# PowerBoard.net
KiCad netlist of a schematic drawn in Altium Designer
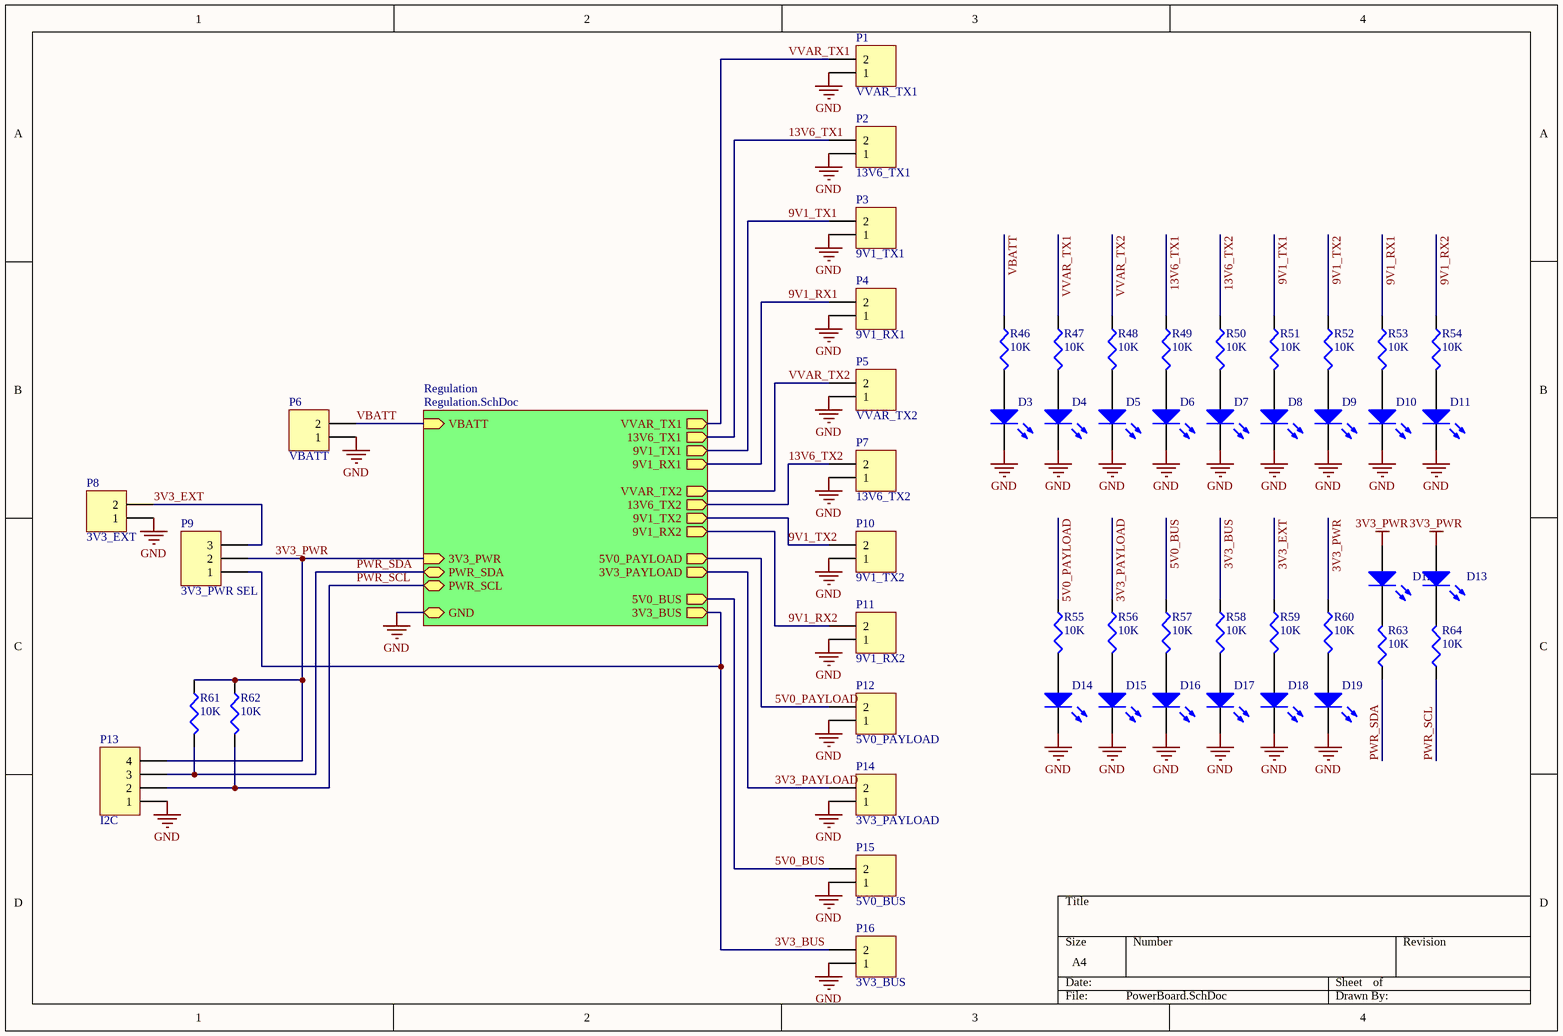
[diagram p0: PowerBoard.SchDoc]

(export (version "E")
  (design (tool "Eeschema 10.0.6"))
  (components
    (comp (ref "D3")
      (value "LED0")
      (footprint "R0805M")
      (description "Typical INFRARED GaAs LED")
      (fields (field (name "PUBLISHER") "Altium Limited"))
      (libsource (lib "Miscellaneous Devices") (part "LED0"))
    )
    (comp (ref "D4")
      (value "LED0")
      (footprint "R0805M")
      (description "Typical INFRARED GaAs LED")
      (fields (field (name "PUBLISHER") "Altium Limited"))
      (libsource (lib "Miscellaneous Devices") (part "LED0"))
    )
    (comp (ref "D5")
      (value "LED0")
      (footprint "R0805M")
      (description "Typical INFRARED GaAs LED")
      (fields (field (name "PUBLISHER") "Altium Limited"))
      (libsource (lib "Miscellaneous Devices") (part "LED0"))
    )
    (comp (ref "D6")
      (value "LED0")
      (footprint "R0805M")
      (description "Typical INFRARED GaAs LED")
      (fields (field (name "PUBLISHER") "Altium Limited"))
      (libsource (lib "Miscellaneous Devices") (part "LED0"))
    )
    (comp (ref "D7")
      (value "LED0")
      (footprint "R0805M")
      (description "Typical INFRARED GaAs LED")
      (fields (field (name "PUBLISHER") "Altium Limited"))
      (libsource (lib "Miscellaneous Devices") (part "LED0"))
    )
    (comp (ref "D8")
      (value "LED0")
      (footprint "R0805M")
      (description "Typical INFRARED GaAs LED")
      (fields (field (name "PUBLISHER") "Altium Limited"))
      (libsource (lib "Miscellaneous Devices") (part "LED0"))
    )
    (comp (ref "D9")
      (value "LED0")
      (footprint "R0805M")
      (description "Typical INFRARED GaAs LED")
      (fields (field (name "PUBLISHER") "Altium Limited"))
      (libsource (lib "Miscellaneous Devices") (part "LED0"))
    )
    (comp (ref "D10")
      (value "LED0")
      (footprint "R0805M")
      (description "Typical INFRARED GaAs LED")
      (fields (field (name "PUBLISHER") "Altium Limited"))
      (libsource (lib "Miscellaneous Devices") (part "LED0"))
    )
    (comp (ref "D11")
      (value "LED0")
      (footprint "R0805M")
      (description "Typical INFRARED GaAs LED")
      (fields (field (name "PUBLISHER") "Altium Limited"))
      (libsource (lib "Miscellaneous Devices") (part "LED0"))
    )
    (comp (ref "D12")
      (value "LED0")
      (footprint "R0805M")
      (description "Typical INFRARED GaAs LED")
      (fields (field (name "PUBLISHER") "Altium Limited"))
      (libsource (lib "Miscellaneous Devices") (part "LED0"))
    )
    (comp (ref "D13")
      (value "LED0")
      (footprint "R0805M")
      (description "Typical INFRARED GaAs LED")
      (fields (field (name "PUBLISHER") "Altium Limited"))
      (libsource (lib "Miscellaneous Devices") (part "LED0"))
    )
    (comp (ref "D14")
      (value "LED0")
      (footprint "R0805M")
      (description "Typical INFRARED GaAs LED")
      (fields (field (name "PUBLISHER") "Altium Limited"))
      (libsource (lib "Miscellaneous Devices") (part "LED0"))
    )
    (comp (ref "D15")
      (value "LED0")
      (footprint "R0805M")
      (description "Typical INFRARED GaAs LED")
      (fields (field (name "PUBLISHER") "Altium Limited"))
      (libsource (lib "Miscellaneous Devices") (part "LED0"))
    )
    (comp (ref "D16")
      (value "LED0")
      (footprint "R0805M")
      (description "Typical INFRARED GaAs LED")
      (fields (field (name "PUBLISHER") "Altium Limited"))
      (libsource (lib "Miscellaneous Devices") (part "LED0"))
    )
    (comp (ref "D17")
      (value "LED0")
      (footprint "R0805M")
      (description "Typical INFRARED GaAs LED")
      (fields (field (name "PUBLISHER") "Altium Limited"))
      (libsource (lib "Miscellaneous Devices") (part "LED0"))
    )
    (comp (ref "D18")
      (value "LED0")
      (footprint "R0805M")
      (description "Typical INFRARED GaAs LED")
      (fields (field (name "PUBLISHER") "Altium Limited"))
      (libsource (lib "Miscellaneous Devices") (part "LED0"))
    )
    (comp (ref "D19")
      (value "LED0")
      (footprint "R0805M")
      (description "Typical INFRARED GaAs LED")
      (fields (field (name "PUBLISHER") "Altium Limited"))
      (libsource (lib "Miscellaneous Devices") (part "LED0"))
    )
    (comp (ref "P1")
      (value "VVAR_TX1")
      (footprint "200MIL TERMINAL")
      (description "Header, 2-Pin")
      (fields (field (name "PUBLISHER") "Altium Limited"))
      (libsource (lib "Miscellaneous Connectors") (part "Header 2"))
    )
    (comp (ref "P2")
      (value "13V6_TX1")
      (footprint "200MIL TERMINAL")
      (description "Header, 2-Pin")
      (fields (field (name "PUBLISHER") "Altium Limited"))
      (libsource (lib "Miscellaneous Connectors") (part "Header 2"))
    )
    (comp (ref "P3")
      (value "9V1_TX1")
      (footprint "200MIL TERMINAL")
      (description "Header, 2-Pin")
      (fields (field (name "PUBLISHER") "Altium Limited"))
      (libsource (lib "Miscellaneous Connectors") (part "Header 2"))
    )
    (comp (ref "P4")
      (value "9V1_RX1")
      (footprint "200MIL TERMINAL")
      (description "Header, 2-Pin")
      (fields (field (name "PUBLISHER") "Altium Limited"))
      (libsource (lib "Miscellaneous Connectors") (part "Header 2"))
    )
    (comp (ref "P5")
      (value "VVAR_TX2")
      (footprint "200MIL TERMINAL")
      (description "Header, 2-Pin")
      (fields (field (name "PUBLISHER") "Altium Limited"))
      (libsource (lib "Miscellaneous Connectors") (part "Header 2"))
    )
    (comp (ref "P6")
      (value "VBATT")
      (footprint "200MIL TERMINAL")
      (description "Header, 2-Pin")
      (fields (field (name "PUBLISHER") "Altium Limited"))
      (libsource (lib "") (part "Header 2_1"))
    )
    (comp (ref "P7")
      (value "13V6_TX2")
      (footprint "200MIL TERMINAL")
      (description "Header, 2-Pin")
      (fields (field (name "PUBLISHER") "Altium Limited"))
      (libsource (lib "Miscellaneous Connectors") (part "Header 2"))
    )
    (comp (ref "P8")
      (value "3V3_EXT")
      (footprint "200MIL TERMINAL")
      (description "Header, 2-Pin")
      (fields (field (name "PUBLISHER") "Altium Limited"))
      (libsource (lib "") (part "Header 2_1"))
    )
    (comp (ref "P9")
      (value "3V3_PWR SEL")
      (footprint "HDR1X3")
      (description "Header, 3-Pin")
      (fields (field (name "PUBLISHER") "Altium Limited"))
      (libsource (lib "Miscellaneous Connectors") (part "Header 3"))
    )
    (comp (ref "P10")
      (value "9V1_TX2")
      (footprint "200MIL TERMINAL")
      (description "Header, 2-Pin")
      (fields (field (name "PUBLISHER") "Altium Limited"))
      (libsource (lib "Miscellaneous Connectors") (part "Header 2"))
    )
    (comp (ref "P11")
      (value "9V1_RX2")
      (footprint "200MIL TERMINAL")
      (description "Header, 2-Pin")
      (fields (field (name "PUBLISHER") "Altium Limited"))
      (libsource (lib "Miscellaneous Connectors") (part "Header 2"))
    )
    (comp (ref "P12")
      (value "5V0_PAYLOAD")
      (footprint "200MIL TERMINAL")
      (description "Header, 2-Pin")
      (fields (field (name "PUBLISHER") "Altium Limited"))
      (libsource (lib "Miscellaneous Connectors") (part "Header 2"))
    )
    (comp (ref "P13")
      (value "I2C")
      (footprint "HDR1X4")
      (description "Header, 4-Pin")
      (fields (field (name "PUBLISHER") "Altium Limited"))
      (libsource (lib "Miscellaneous Connectors") (part "Header 4"))
    )
    (comp (ref "P14")
      (value "3V3_PAYLOAD")
      (footprint "200MIL TERMINAL")
      (description "Header, 2-Pin")
      (fields (field (name "PUBLISHER") "Altium Limited"))
      (libsource (lib "Miscellaneous Connectors") (part "Header 2"))
    )
    (comp (ref "P15")
      (value "5V0_BUS")
      (footprint "200MIL TERMINAL")
      (description "Header, 2-Pin")
      (fields (field (name "PUBLISHER") "Altium Limited"))
      (libsource (lib "Miscellaneous Connectors") (part "Header 2"))
    )
    (comp (ref "P16")
      (value "3V3_BUS")
      (footprint "200MIL TERMINAL")
      (description "Header, 2-Pin")
      (fields (field (name "PUBLISHER") "Altium Limited"))
      (libsource (lib "Miscellaneous Connectors") (part "Header 2"))
    )
    (comp (ref "R46")
      (value "10K")
      (footprint "R0402M")
      (description "Resistor")
      (fields (field (name "PUBLISHER") "Altium Limited"))
      (libsource (lib "Miscellaneous Devices") (part "Res3"))
    )
    (comp (ref "R47")
      (value "10K")
      (footprint "R0402M")
      (description "Resistor")
      (fields (field (name "PUBLISHER") "Altium Limited"))
      (libsource (lib "Miscellaneous Devices") (part "Res3"))
    )
    (comp (ref "R48")
      (value "10K")
      (footprint "R0402M")
      (description "Resistor")
      (fields (field (name "PUBLISHER") "Altium Limited"))
      (libsource (lib "Miscellaneous Devices") (part "Res3"))
    )
    (comp (ref "R49")
      (value "10K")
      (footprint "R0402M")
      (description "Resistor")
      (fields (field (name "PUBLISHER") "Altium Limited"))
      (libsource (lib "Miscellaneous Devices") (part "Res3"))
    )
    (comp (ref "R50")
      (value "10K")
      (footprint "R0402M")
      (description "Resistor")
      (fields (field (name "PUBLISHER") "Altium Limited"))
      (libsource (lib "Miscellaneous Devices") (part "Res3"))
    )
    (comp (ref "R51")
      (value "10K")
      (footprint "R0402M")
      (description "Resistor")
      (fields (field (name "PUBLISHER") "Altium Limited"))
      (libsource (lib "Miscellaneous Devices") (part "Res3"))
    )
    (comp (ref "R52")
      (value "10K")
      (footprint "R0402M")
      (description "Resistor")
      (fields (field (name "PUBLISHER") "Altium Limited"))
      (libsource (lib "Miscellaneous Devices") (part "Res3"))
    )
    (comp (ref "R53")
      (value "10K")
      (footprint "R0402M")
      (description "Resistor")
      (fields (field (name "PUBLISHER") "Altium Limited"))
      (libsource (lib "Miscellaneous Devices") (part "Res3"))
    )
    (comp (ref "R54")
      (value "10K")
      (footprint "R0402M")
      (description "Resistor")
      (fields (field (name "PUBLISHER") "Altium Limited"))
      (libsource (lib "Miscellaneous Devices") (part "Res3"))
    )
    (comp (ref "R55")
      (value "10K")
      (footprint "R0402M")
      (description "Resistor")
      (fields (field (name "PUBLISHER") "Altium Limited"))
      (libsource (lib "Miscellaneous Devices") (part "Res3"))
    )
    (comp (ref "R56")
      (value "10K")
      (footprint "R0402M")
      (description "Resistor")
      (fields (field (name "PUBLISHER") "Altium Limited"))
      (libsource (lib "Miscellaneous Devices") (part "Res3"))
    )
    (comp (ref "R57")
      (value "10K")
      (footprint "R0402M")
      (description "Resistor")
      (fields (field (name "PUBLISHER") "Altium Limited"))
      (libsource (lib "Miscellaneous Devices") (part "Res3"))
    )
    (comp (ref "R58")
      (value "10K")
      (footprint "R0402M")
      (description "Resistor")
      (fields (field (name "PUBLISHER") "Altium Limited"))
      (libsource (lib "Miscellaneous Devices") (part "Res3"))
    )
    (comp (ref "R59")
      (value "10K")
      (footprint "R0402M")
      (description "Resistor")
      (fields (field (name "PUBLISHER") "Altium Limited"))
      (libsource (lib "Miscellaneous Devices") (part "Res3"))
    )
    (comp (ref "R60")
      (value "10K")
      (footprint "R0402M")
      (description "Resistor")
      (fields (field (name "PUBLISHER") "Altium Limited"))
      (libsource (lib "Miscellaneous Devices") (part "Res3"))
    )
    (comp (ref "R61")
      (value "10K")
      (footprint "R0402M")
      (description "Resistor")
      (fields (field (name "PUBLISHER") "Altium Limited"))
      (libsource (lib "Miscellaneous Devices") (part "Res3"))
    )
    (comp (ref "R62")
      (value "10K")
      (footprint "R0402M")
      (description "Resistor")
      (fields (field (name "PUBLISHER") "Altium Limited"))
      (libsource (lib "Miscellaneous Devices") (part "Res3"))
    )
    (comp (ref "R63")
      (value "10K")
      (footprint "R0402M")
      (description "Resistor")
      (fields (field (name "PUBLISHER") "Altium Limited"))
      (libsource (lib "Miscellaneous Devices") (part "Res3"))
    )
    (comp (ref "R64")
      (value "10K")
      (footprint "R0402M")
      (description "Resistor")
      (fields (field (name "PUBLISHER") "Altium Limited"))
      (libsource (lib "Miscellaneous Devices") (part "Res3"))
    )
  )
  (nets
    (net (code "1") (name "/3V3_BUS") (class "Default")
      (node (ref "P16") (pin "2") (pinfunction "2_2") (pintype "passive"))
      (node (ref "P9") (pin "1") (pinfunction "1_1") (pintype "passive"))
      (node (ref "R58") (pin "1") (pinfunction "1_1") (pintype "passive"))
    )
    (net (code "2") (name "/3V3_EXT") (class "Default")
      (node (ref "P8") (pin "2") (pinfunction "2_2") (pintype "passive"))
      (node (ref "P9") (pin "3") (pinfunction "3_3") (pintype "passive"))
      (node (ref "R59") (pin "1") (pinfunction "1_1") (pintype "passive"))
    )
    (net (code "3") (name "/3V3_PAYLOAD") (class "Default")
      (node (ref "P14") (pin "2") (pinfunction "2_2") (pintype "passive"))
      (node (ref "R56") (pin "1") (pinfunction "1_1") (pintype "passive"))
    )
    (net (code "4") (name "/5V0_BUS") (class "Default")
      (node (ref "P15") (pin "2") (pinfunction "2_2") (pintype "passive"))
      (node (ref "R57") (pin "1") (pinfunction "1_1") (pintype "passive"))
    )
    (net (code "5") (name "/5V0_PAYLOAD") (class "Default")
      (node (ref "P12") (pin "2") (pinfunction "2_2") (pintype "passive"))
      (node (ref "R55") (pin "1") (pinfunction "1_1") (pintype "passive"))
    )
    (net (code "6") (name "/9V1_RX1") (class "Default")
      (node (ref "P4") (pin "2") (pinfunction "2_2") (pintype "passive"))
      (node (ref "R53") (pin "1") (pinfunction "1_1") (pintype "passive"))
    )
    (net (code "7") (name "/9V1_RX2") (class "Default")
      (node (ref "P11") (pin "2") (pinfunction "2_2") (pintype "passive"))
      (node (ref "R54") (pin "1") (pinfunction "1_1") (pintype "passive"))
    )
    (net (code "8") (name "/9V1_TX1") (class "Default")
      (node (ref "P3") (pin "2") (pinfunction "2_2") (pintype "passive"))
      (node (ref "R51") (pin "1") (pinfunction "1_1") (pintype "passive"))
    )
    (net (code "9") (name "/9V1_TX2") (class "Default")
      (node (ref "P10") (pin "2") (pinfunction "2_2") (pintype "passive"))
      (node (ref "R52") (pin "1") (pinfunction "1_1") (pintype "passive"))
    )
    (net (code "10") (name "/13V6_TX1") (class "Default")
      (node (ref "P2") (pin "2") (pinfunction "2_2") (pintype "passive"))
      (node (ref "R49") (pin "1") (pinfunction "1_1") (pintype "passive"))
    )
    (net (code "11") (name "/13V6_TX2") (class "Default")
      (node (ref "P7") (pin "2") (pinfunction "2_2") (pintype "passive"))
      (node (ref "R50") (pin "1") (pinfunction "1_1") (pintype "passive"))
    )
    (net (code "12") (name "/PWR_SCL") (class "Default")
      (node (ref "P13") (pin "2") (pinfunction "2_2") (pintype "passive"))
      (node (ref "R62") (pin "2") (pinfunction "2_2") (pintype "passive"))
      (node (ref "R64") (pin "1") (pinfunction "1_1") (pintype "passive"))
    )
    (net (code "13") (name "/PWR_SDA") (class "Default")
      (node (ref "P13") (pin "3") (pinfunction "3_3") (pintype "passive"))
      (node (ref "R61") (pin "2") (pinfunction "2_2") (pintype "passive"))
      (node (ref "R63") (pin "1") (pinfunction "1_1") (pintype "passive"))
    )
    (net (code "14") (name "/VBATT") (class "Default")
      (node (ref "P6") (pin "2") (pinfunction "2_2") (pintype "passive"))
      (node (ref "R46") (pin "1") (pinfunction "1_1") (pintype "passive"))
    )
    (net (code "15") (name "/VVAR_TX1") (class "Default")
      (node (ref "P1") (pin "2") (pinfunction "2_2") (pintype "passive"))
      (node (ref "R47") (pin "1") (pinfunction "1_1") (pintype "passive"))
    )
    (net (code "16") (name "/VVAR_TX2") (class "Default")
      (node (ref "P5") (pin "2") (pinfunction "2_2") (pintype "passive"))
      (node (ref "R48") (pin "1") (pinfunction "1_1") (pintype "passive"))
    )
    (net (code "17") (name "3V3_PWR") (class "Default")
      (node (ref "D12") (pin "1") (pinfunction "A_1") (pintype "passive"))
      (node (ref "D13") (pin "1") (pinfunction "A_1") (pintype "passive"))
      (node (ref "P13") (pin "4") (pinfunction "4_4") (pintype "passive"))
      (node (ref "P9") (pin "2") (pinfunction "2_2") (pintype "passive"))
      (node (ref "R60") (pin "1") (pinfunction "1_1") (pintype "passive"))
      (node (ref "R61") (pin "1") (pinfunction "1_1") (pintype "passive"))
      (node (ref "R62") (pin "1") (pinfunction "1_1") (pintype "passive"))
    )
    (net (code "18") (name "GND") (class "Default")
      (node (ref "D10") (pin "2") (pinfunction "K_2") (pintype "passive"))
      (node (ref "D11") (pin "2") (pinfunction "K_2") (pintype "passive"))
      (node (ref "D14") (pin "2") (pinfunction "K_2") (pintype "passive"))
      (node (ref "D15") (pin "2") (pinfunction "K_2") (pintype "passive"))
      (node (ref "D16") (pin "2") (pinfunction "K_2") (pintype "passive"))
      (node (ref "D17") (pin "2") (pinfunction "K_2") (pintype "passive"))
      (node (ref "D18") (pin "2") (pinfunction "K_2") (pintype "passive"))
      (node (ref "D19") (pin "2") (pinfunction "K_2") (pintype "passive"))
      (node (ref "D3") (pin "2") (pinfunction "K_2") (pintype "passive"))
      (node (ref "D4") (pin "2") (pinfunction "K_2") (pintype "passive"))
      (node (ref "D5") (pin "2") (pinfunction "K_2") (pintype "passive"))
      (node (ref "D6") (pin "2") (pinfunction "K_2") (pintype "passive"))
      (node (ref "D7") (pin "2") (pinfunction "K_2") (pintype "passive"))
      (node (ref "D8") (pin "2") (pinfunction "K_2") (pintype "passive"))
      (node (ref "D9") (pin "2") (pinfunction "K_2") (pintype "passive"))
      (node (ref "P1") (pin "1") (pinfunction "1_1") (pintype "passive"))
      (node (ref "P10") (pin "1") (pinfunction "1_1") (pintype "passive"))
      (node (ref "P11") (pin "1") (pinfunction "1_1") (pintype "passive"))
      (node (ref "P12") (pin "1") (pinfunction "1_1") (pintype "passive"))
      (node (ref "P13") (pin "1") (pinfunction "1_1") (pintype "passive"))
      (node (ref "P14") (pin "1") (pinfunction "1_1") (pintype "passive"))
      (node (ref "P15") (pin "1") (pinfunction "1_1") (pintype "passive"))
      (node (ref "P16") (pin "1") (pinfunction "1_1") (pintype "passive"))
      (node (ref "P2") (pin "1") (pinfunction "1_1") (pintype "passive"))
      (node (ref "P3") (pin "1") (pinfunction "1_1") (pintype "passive"))
      (node (ref "P4") (pin "1") (pinfunction "1_1") (pintype "passive"))
      (node (ref "P5") (pin "1") (pinfunction "1_1") (pintype "passive"))
      (node (ref "P6") (pin "1") (pinfunction "1_1") (pintype "passive"))
      (node (ref "P7") (pin "1") (pinfunction "1_1") (pintype "passive"))
      (node (ref "P8") (pin "1") (pinfunction "1_1") (pintype "passive"))
    )
    (net (code "19") (name "Net-(D3-A)") (class "Default")
      (node (ref "D3") (pin "1") (pinfunction "A_1") (pintype "passive"))
      (node (ref "R46") (pin "2") (pinfunction "2_2") (pintype "passive"))
    )
    (net (code "20") (name "Net-(D4-A)") (class "Default")
      (node (ref "D4") (pin "1") (pinfunction "A_1") (pintype "passive"))
      (node (ref "R47") (pin "2") (pinfunction "2_2") (pintype "passive"))
    )
    (net (code "21") (name "Net-(D5-A)") (class "Default")
      (node (ref "D5") (pin "1") (pinfunction "A_1") (pintype "passive"))
      (node (ref "R48") (pin "2") (pinfunction "2_2") (pintype "passive"))
    )
    (net (code "22") (name "Net-(D6-A)") (class "Default")
      (node (ref "D6") (pin "1") (pinfunction "A_1") (pintype "passive"))
      (node (ref "R49") (pin "2") (pinfunction "2_2") (pintype "passive"))
    )
    (net (code "23") (name "Net-(D7-A)") (class "Default")
      (node (ref "D7") (pin "1") (pinfunction "A_1") (pintype "passive"))
      (node (ref "R50") (pin "2") (pinfunction "2_2") (pintype "passive"))
    )
    (net (code "24") (name "Net-(D8-A)") (class "Default")
      (node (ref "D8") (pin "1") (pinfunction "A_1") (pintype "passive"))
      (node (ref "R51") (pin "2") (pinfunction "2_2") (pintype "passive"))
    )
    (net (code "25") (name "Net-(D9-A)") (class "Default")
      (node (ref "D9") (pin "1") (pinfunction "A_1") (pintype "passive"))
      (node (ref "R52") (pin "2") (pinfunction "2_2") (pintype "passive"))
    )
    (net (code "26") (name "Net-(D10-A)") (class "Default")
      (node (ref "D10") (pin "1") (pinfunction "A_1") (pintype "passive"))
      (node (ref "R53") (pin "2") (pinfunction "2_2") (pintype "passive"))
    )
    (net (code "27") (name "Net-(D11-A)") (class "Default")
      (node (ref "D11") (pin "1") (pinfunction "A_1") (pintype "passive"))
      (node (ref "R54") (pin "2") (pinfunction "2_2") (pintype "passive"))
    )
    (net (code "28") (name "Net-(D12-K)") (class "Default")
      (node (ref "D12") (pin "2") (pinfunction "K_2") (pintype "passive"))
      (node (ref "R63") (pin "2") (pinfunction "2_2") (pintype "passive"))
    )
    (net (code "29") (name "Net-(D13-K)") (class "Default")
      (node (ref "D13") (pin "2") (pinfunction "K_2") (pintype "passive"))
      (node (ref "R64") (pin "2") (pinfunction "2_2") (pintype "passive"))
    )
    (net (code "30") (name "Net-(D14-A)") (class "Default")
      (node (ref "D14") (pin "1") (pinfunction "A_1") (pintype "passive"))
      (node (ref "R55") (pin "2") (pinfunction "2_2") (pintype "passive"))
    )
    (net (code "31") (name "Net-(D15-A)") (class "Default")
      (node (ref "D15") (pin "1") (pinfunction "A_1") (pintype "passive"))
      (node (ref "R56") (pin "2") (pinfunction "2_2") (pintype "passive"))
    )
    (net (code "32") (name "Net-(D16-A)") (class "Default")
      (node (ref "D16") (pin "1") (pinfunction "A_1") (pintype "passive"))
      (node (ref "R57") (pin "2") (pinfunction "2_2") (pintype "passive"))
    )
    (net (code "33") (name "Net-(D17-A)") (class "Default")
      (node (ref "D17") (pin "1") (pinfunction "A_1") (pintype "passive"))
      (node (ref "R58") (pin "2") (pinfunction "2_2") (pintype "passive"))
    )
    (net (code "34") (name "Net-(D18-A)") (class "Default")
      (node (ref "D18") (pin "1") (pinfunction "A_1") (pintype "passive"))
      (node (ref "R59") (pin "2") (pinfunction "2_2") (pintype "passive"))
    )
    (net (code "35") (name "Net-(D19-A)") (class "Default")
      (node (ref "D19") (pin "1") (pinfunction "A_1") (pintype "passive"))
      (node (ref "R60") (pin "2") (pinfunction "2_2") (pintype "passive"))
    )
  )
)
